# LED_004.net
KiCad netlist of a schematic drawn in EAGLE
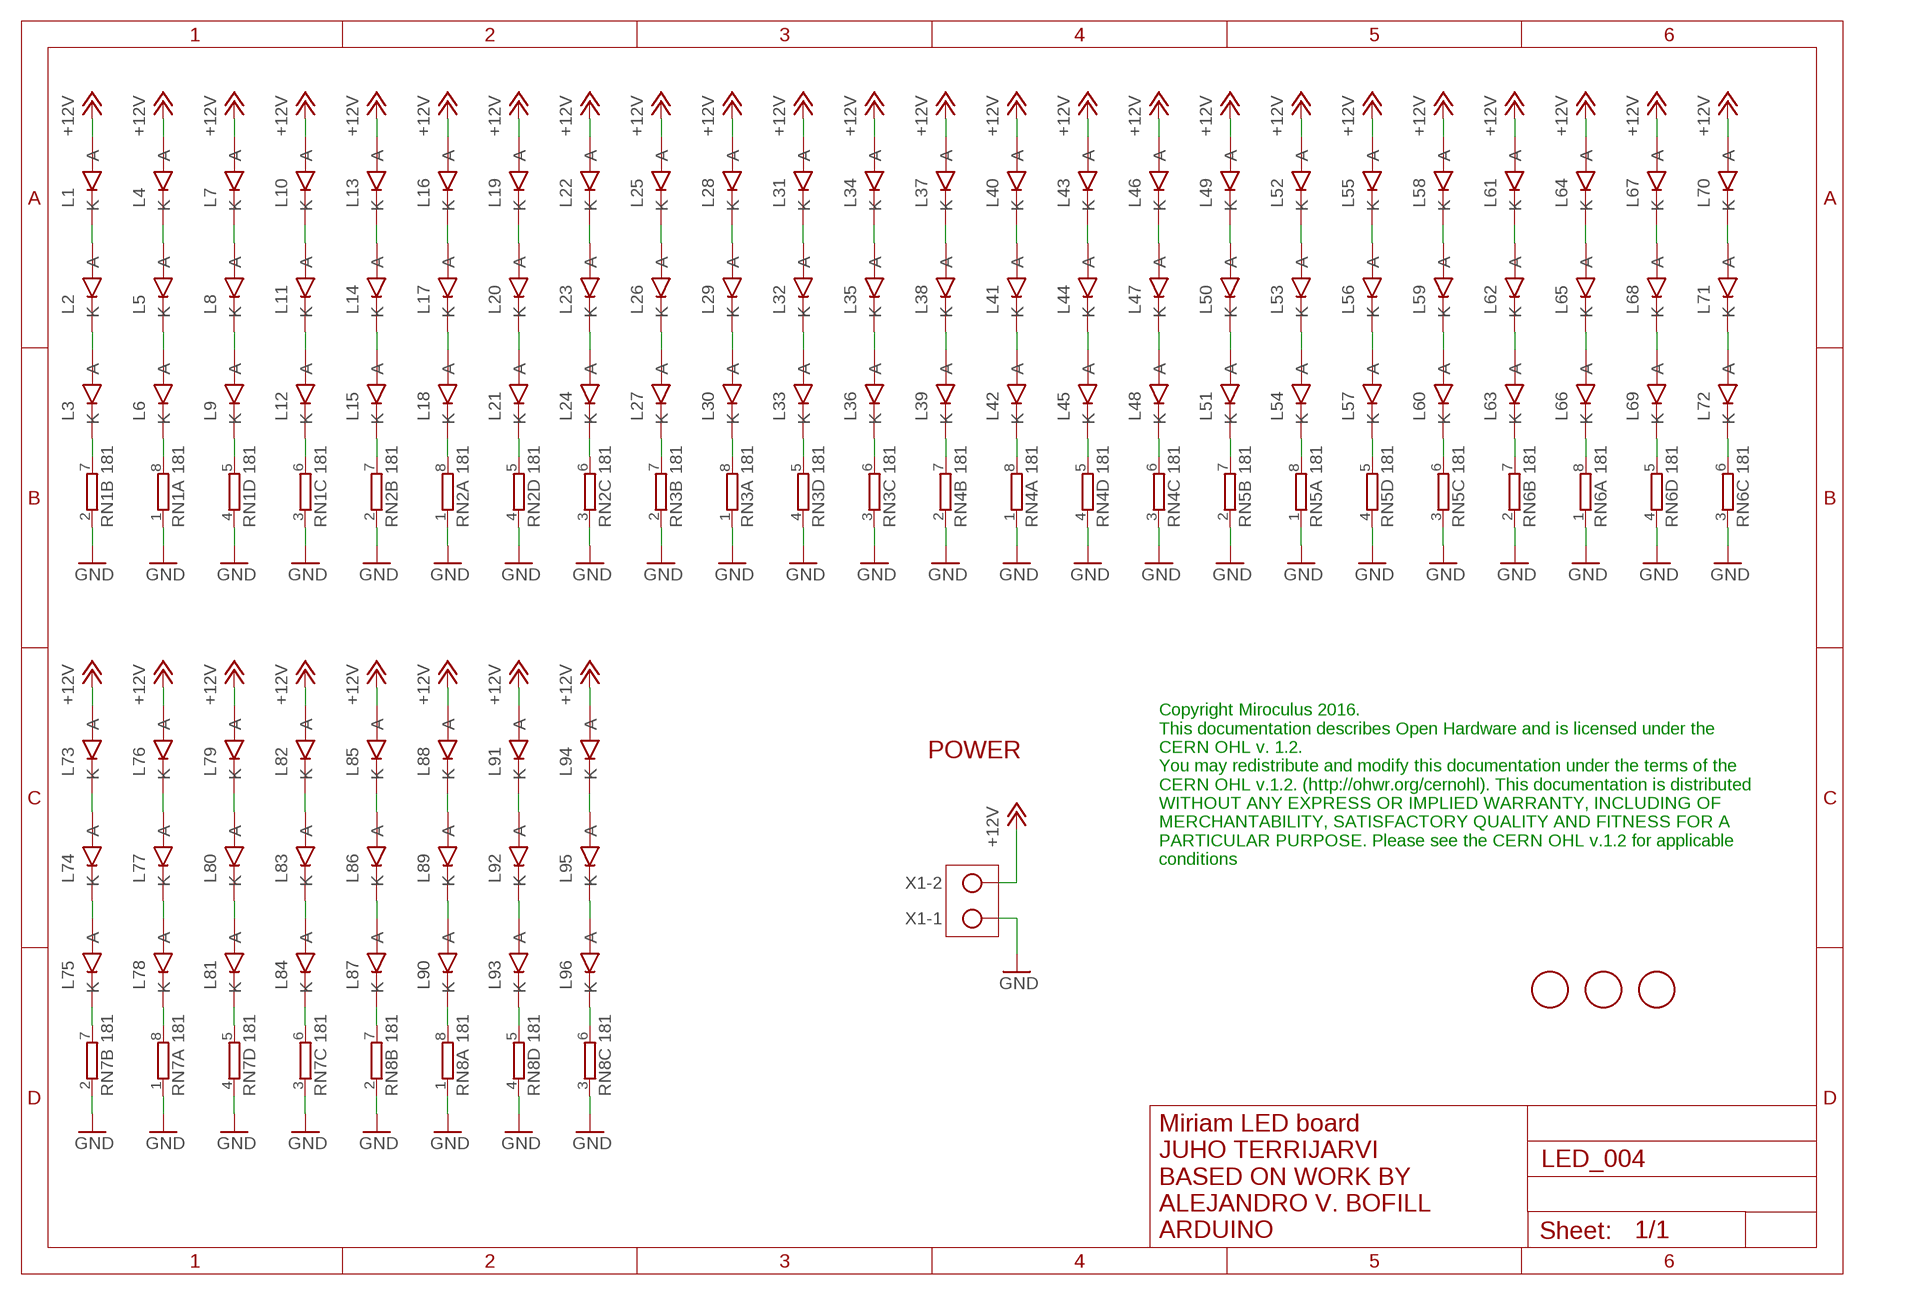
[diagram p0: schematic, sheet 1]

(export (version "E")
  (design (tool "Eeschema 10.0.6"))
  (components
    (comp (ref "FD1")
      (value "FIDUCIALMOUNT")
      (footprint "eagle-import:FIDUCIA-MOUNT")
      (libsource (lib "eagle-import") (part "FIDUCIALMOUNT"))
    )
    (comp (ref "FD2")
      (value "FIDUCIALMOUNT")
      (footprint "eagle-import:FIDUCIA-MOUNT")
      (libsource (lib "eagle-import") (part "FIDUCIALMOUNT"))
    )
    (comp (ref "FD3")
      (value "FIDUCIALMOUNT")
      (footprint "eagle-import:FIDUCIA-MOUNT")
      (libsource (lib "eagle-import") (part "FIDUCIALMOUNT"))
    )
    (comp (ref "L1")
      (value "KA-2810AQBS-G")
      (footprint "eagle-import:LED_0.2")
      (libsource (lib "eagle-import") (part "LED_0.2"))
    )
    (comp (ref "L2")
      (value "KA-2810AQBS-G")
      (footprint "eagle-import:LED_0.2")
      (libsource (lib "eagle-import") (part "LED_0.2"))
    )
    (comp (ref "L3")
      (value "KA-2810AQBS-G")
      (footprint "eagle-import:LED_0.2")
      (libsource (lib "eagle-import") (part "LED_0.2"))
    )
    (comp (ref "L4")
      (value "KA-2810AQBS-G")
      (footprint "eagle-import:LED_0.2")
      (libsource (lib "eagle-import") (part "LED_0.2"))
    )
    (comp (ref "L5")
      (value "KA-2810AQBS-G")
      (footprint "eagle-import:LED_0.2")
      (libsource (lib "eagle-import") (part "LED_0.2"))
    )
    (comp (ref "L6")
      (value "KA-2810AQBS-G")
      (footprint "eagle-import:LED_0.2")
      (libsource (lib "eagle-import") (part "LED_0.2"))
    )
    (comp (ref "L7")
      (value "KA-2810AQBS-G")
      (footprint "eagle-import:LED_0.2")
      (libsource (lib "eagle-import") (part "LED_0.2"))
    )
    (comp (ref "L8")
      (value "KA-2810AQBS-G")
      (footprint "eagle-import:LED_0.2")
      (libsource (lib "eagle-import") (part "LED_0.2"))
    )
    (comp (ref "L9")
      (value "KA-2810AQBS-G")
      (footprint "eagle-import:LED_0.2")
      (libsource (lib "eagle-import") (part "LED_0.2"))
    )
    (comp (ref "L10")
      (value "KA-2810AQBS-G")
      (footprint "eagle-import:LED_0.2")
      (libsource (lib "eagle-import") (part "LED_0.2"))
    )
    (comp (ref "L11")
      (value "KA-2810AQBS-G")
      (footprint "eagle-import:LED_0.2")
      (libsource (lib "eagle-import") (part "LED_0.2"))
    )
    (comp (ref "L12")
      (value "KA-2810AQBS-G")
      (footprint "eagle-import:LED_0.2")
      (libsource (lib "eagle-import") (part "LED_0.2"))
    )
    (comp (ref "L13")
      (value "KA-2810AQBS-G")
      (footprint "eagle-import:LED_0.2")
      (libsource (lib "eagle-import") (part "LED_0.2"))
    )
    (comp (ref "L14")
      (value "KA-2810AQBS-G")
      (footprint "eagle-import:LED_0.2")
      (libsource (lib "eagle-import") (part "LED_0.2"))
    )
    (comp (ref "L15")
      (value "KA-2810AQBS-G")
      (footprint "eagle-import:LED_0.2")
      (libsource (lib "eagle-import") (part "LED_0.2"))
    )
    (comp (ref "L16")
      (value "KA-2810AQBS-G")
      (footprint "eagle-import:LED_0.2")
      (libsource (lib "eagle-import") (part "LED_0.2"))
    )
    (comp (ref "L17")
      (value "KA-2810AQBS-G")
      (footprint "eagle-import:LED_0.2")
      (libsource (lib "eagle-import") (part "LED_0.2"))
    )
    (comp (ref "L18")
      (value "KA-2810AQBS-G")
      (footprint "eagle-import:LED_0.2")
      (libsource (lib "eagle-import") (part "LED_0.2"))
    )
    (comp (ref "L19")
      (value "KA-2810AQBS-G")
      (footprint "eagle-import:LED_0.2")
      (libsource (lib "eagle-import") (part "LED_0.2"))
    )
    (comp (ref "L20")
      (value "KA-2810AQBS-G")
      (footprint "eagle-import:LED_0.2")
      (libsource (lib "eagle-import") (part "LED_0.2"))
    )
    (comp (ref "L21")
      (value "KA-2810AQBS-G")
      (footprint "eagle-import:LED_0.2")
      (libsource (lib "eagle-import") (part "LED_0.2"))
    )
    (comp (ref "L22")
      (value "KA-2810AQBS-G")
      (footprint "eagle-import:LED_0.2")
      (libsource (lib "eagle-import") (part "LED_0.2"))
    )
    (comp (ref "L23")
      (value "KA-2810AQBS-G")
      (footprint "eagle-import:LED_0.2")
      (libsource (lib "eagle-import") (part "LED_0.2"))
    )
    (comp (ref "L24")
      (value "KA-2810AQBS-G")
      (footprint "eagle-import:LED_0.2")
      (libsource (lib "eagle-import") (part "LED_0.2"))
    )
    (comp (ref "L25")
      (value "KA-2810AQBS-G")
      (footprint "eagle-import:LED_0.2")
      (libsource (lib "eagle-import") (part "LED_0.2"))
    )
    (comp (ref "L26")
      (value "KA-2810AQBS-G")
      (footprint "eagle-import:LED_0.2")
      (libsource (lib "eagle-import") (part "LED_0.2"))
    )
    (comp (ref "L27")
      (value "KA-2810AQBS-G")
      (footprint "eagle-import:LED_0.2")
      (libsource (lib "eagle-import") (part "LED_0.2"))
    )
    (comp (ref "L28")
      (value "KA-2810AQBS-G")
      (footprint "eagle-import:LED_0.2")
      (libsource (lib "eagle-import") (part "LED_0.2"))
    )
    (comp (ref "L29")
      (value "KA-2810AQBS-G")
      (footprint "eagle-import:LED_0.2")
      (libsource (lib "eagle-import") (part "LED_0.2"))
    )
    (comp (ref "L30")
      (value "KA-2810AQBS-G")
      (footprint "eagle-import:LED_0.2")
      (libsource (lib "eagle-import") (part "LED_0.2"))
    )
    (comp (ref "L31")
      (value "KA-2810AQBS-G")
      (footprint "eagle-import:LED_0.2")
      (libsource (lib "eagle-import") (part "LED_0.2"))
    )
    (comp (ref "L32")
      (value "KA-2810AQBS-G")
      (footprint "eagle-import:LED_0.2")
      (libsource (lib "eagle-import") (part "LED_0.2"))
    )
    (comp (ref "L33")
      (value "KA-2810AQBS-G")
      (footprint "eagle-import:LED_0.2")
      (libsource (lib "eagle-import") (part "LED_0.2"))
    )
    (comp (ref "L34")
      (value "KA-2810AQBS-G")
      (footprint "eagle-import:LED_0.2")
      (libsource (lib "eagle-import") (part "LED_0.2"))
    )
    (comp (ref "L35")
      (value "KA-2810AQBS-G")
      (footprint "eagle-import:LED_0.2")
      (libsource (lib "eagle-import") (part "LED_0.2"))
    )
    (comp (ref "L36")
      (value "KA-2810AQBS-G")
      (footprint "eagle-import:LED_0.2")
      (libsource (lib "eagle-import") (part "LED_0.2"))
    )
    (comp (ref "L37")
      (value "KA-2810AQBS-G")
      (footprint "eagle-import:LED_0.2")
      (libsource (lib "eagle-import") (part "LED_0.2"))
    )
    (comp (ref "L38")
      (value "KA-2810AQBS-G")
      (footprint "eagle-import:LED_0.2")
      (libsource (lib "eagle-import") (part "LED_0.2"))
    )
    (comp (ref "L39")
      (value "KA-2810AQBS-G")
      (footprint "eagle-import:LED_0.2")
      (libsource (lib "eagle-import") (part "LED_0.2"))
    )
    (comp (ref "L40")
      (value "KA-2810AQBS-G")
      (footprint "eagle-import:LED_0.2")
      (libsource (lib "eagle-import") (part "LED_0.2"))
    )
    (comp (ref "L41")
      (value "KA-2810AQBS-G")
      (footprint "eagle-import:LED_0.2")
      (libsource (lib "eagle-import") (part "LED_0.2"))
    )
    (comp (ref "L42")
      (value "KA-2810AQBS-G")
      (footprint "eagle-import:LED_0.2")
      (libsource (lib "eagle-import") (part "LED_0.2"))
    )
    (comp (ref "L43")
      (value "KA-2810AQBS-G")
      (footprint "eagle-import:LED_0.2")
      (libsource (lib "eagle-import") (part "LED_0.2"))
    )
    (comp (ref "L44")
      (value "KA-2810AQBS-G")
      (footprint "eagle-import:LED_0.2")
      (libsource (lib "eagle-import") (part "LED_0.2"))
    )
    (comp (ref "L45")
      (value "KA-2810AQBS-G")
      (footprint "eagle-import:LED_0.2")
      (libsource (lib "eagle-import") (part "LED_0.2"))
    )
    (comp (ref "L46")
      (value "KA-2810AQBS-G")
      (footprint "eagle-import:LED_0.2")
      (libsource (lib "eagle-import") (part "LED_0.2"))
    )
    (comp (ref "L47")
      (value "KA-2810AQBS-G")
      (footprint "eagle-import:LED_0.2")
      (libsource (lib "eagle-import") (part "LED_0.2"))
    )
    (comp (ref "L48")
      (value "KA-2810AQBS-G")
      (footprint "eagle-import:LED_0.2")
      (libsource (lib "eagle-import") (part "LED_0.2"))
    )
    (comp (ref "L49")
      (value "KA-2810AQBS-G")
      (footprint "eagle-import:LED_0.2")
      (libsource (lib "eagle-import") (part "LED_0.2"))
    )
    (comp (ref "L50")
      (value "KA-2810AQBS-G")
      (footprint "eagle-import:LED_0.2")
      (libsource (lib "eagle-import") (part "LED_0.2"))
    )
    (comp (ref "L51")
      (value "KA-2810AQBS-G")
      (footprint "eagle-import:LED_0.2")
      (libsource (lib "eagle-import") (part "LED_0.2"))
    )
    (comp (ref "L52")
      (value "KA-2810AQBS-G")
      (footprint "eagle-import:LED_0.2")
      (libsource (lib "eagle-import") (part "LED_0.2"))
    )
    (comp (ref "L53")
      (value "KA-2810AQBS-G")
      (footprint "eagle-import:LED_0.2")
      (libsource (lib "eagle-import") (part "LED_0.2"))
    )
    (comp (ref "L54")
      (value "KA-2810AQBS-G")
      (footprint "eagle-import:LED_0.2")
      (libsource (lib "eagle-import") (part "LED_0.2"))
    )
    (comp (ref "L55")
      (value "KA-2810AQBS-G")
      (footprint "eagle-import:LED_0.2")
      (libsource (lib "eagle-import") (part "LED_0.2"))
    )
    (comp (ref "L56")
      (value "KA-2810AQBS-G")
      (footprint "eagle-import:LED_0.2")
      (libsource (lib "eagle-import") (part "LED_0.2"))
    )
    (comp (ref "L57")
      (value "KA-2810AQBS-G")
      (footprint "eagle-import:LED_0.2")
      (libsource (lib "eagle-import") (part "LED_0.2"))
    )
    (comp (ref "L58")
      (value "KA-2810AQBS-G")
      (footprint "eagle-import:LED_0.2")
      (libsource (lib "eagle-import") (part "LED_0.2"))
    )
    (comp (ref "L59")
      (value "KA-2810AQBS-G")
      (footprint "eagle-import:LED_0.2")
      (libsource (lib "eagle-import") (part "LED_0.2"))
    )
    (comp (ref "L60")
      (value "KA-2810AQBS-G")
      (footprint "eagle-import:LED_0.2")
      (libsource (lib "eagle-import") (part "LED_0.2"))
    )
    (comp (ref "L61")
      (value "KA-2810AQBS-G")
      (footprint "eagle-import:LED_0.2")
      (libsource (lib "eagle-import") (part "LED_0.2"))
    )
    (comp (ref "L62")
      (value "KA-2810AQBS-G")
      (footprint "eagle-import:LED_0.2")
      (libsource (lib "eagle-import") (part "LED_0.2"))
    )
    (comp (ref "L63")
      (value "KA-2810AQBS-G")
      (footprint "eagle-import:LED_0.2")
      (libsource (lib "eagle-import") (part "LED_0.2"))
    )
    (comp (ref "L64")
      (value "KA-2810AQBS-G")
      (footprint "eagle-import:LED_0.2")
      (libsource (lib "eagle-import") (part "LED_0.2"))
    )
    (comp (ref "L65")
      (value "KA-2810AQBS-G")
      (footprint "eagle-import:LED_0.2")
      (libsource (lib "eagle-import") (part "LED_0.2"))
    )
    (comp (ref "L66")
      (value "KA-2810AQBS-G")
      (footprint "eagle-import:LED_0.2")
      (libsource (lib "eagle-import") (part "LED_0.2"))
    )
    (comp (ref "L67")
      (value "KA-2810AQBS-G")
      (footprint "eagle-import:LED_0.2")
      (libsource (lib "eagle-import") (part "LED_0.2"))
    )
    (comp (ref "L68")
      (value "KA-2810AQBS-G")
      (footprint "eagle-import:LED_0.2")
      (libsource (lib "eagle-import") (part "LED_0.2"))
    )
    (comp (ref "L69")
      (value "KA-2810AQBS-G")
      (footprint "eagle-import:LED_0.2")
      (libsource (lib "eagle-import") (part "LED_0.2"))
    )
    (comp (ref "L70")
      (value "KA-2810AQBS-G")
      (footprint "eagle-import:LED_0.2")
      (libsource (lib "eagle-import") (part "LED_0.2"))
    )
    (comp (ref "L71")
      (value "KA-2810AQBS-G")
      (footprint "eagle-import:LED_0.2")
      (libsource (lib "eagle-import") (part "LED_0.2"))
    )
    (comp (ref "L72")
      (value "KA-2810AQBS-G")
      (footprint "eagle-import:LED_0.2")
      (libsource (lib "eagle-import") (part "LED_0.2"))
    )
    (comp (ref "L73")
      (value "KA-2810AQBS-G")
      (footprint "eagle-import:LED_0.2")
      (libsource (lib "eagle-import") (part "LED_0.2"))
    )
    (comp (ref "L74")
      (value "KA-2810AQBS-G")
      (footprint "eagle-import:LED_0.2")
      (libsource (lib "eagle-import") (part "LED_0.2"))
    )
    (comp (ref "L75")
      (value "KA-2810AQBS-G")
      (footprint "eagle-import:LED_0.2")
      (libsource (lib "eagle-import") (part "LED_0.2"))
    )
    (comp (ref "L76")
      (value "KA-2810AQBS-G")
      (footprint "eagle-import:LED_0.2")
      (libsource (lib "eagle-import") (part "LED_0.2"))
    )
    (comp (ref "L77")
      (value "KA-2810AQBS-G")
      (footprint "eagle-import:LED_0.2")
      (libsource (lib "eagle-import") (part "LED_0.2"))
    )
    (comp (ref "L78")
      (value "KA-2810AQBS-G")
      (footprint "eagle-import:LED_0.2")
      (libsource (lib "eagle-import") (part "LED_0.2"))
    )
    (comp (ref "L79")
      (value "KA-2810AQBS-G")
      (footprint "eagle-import:LED_0.2")
      (libsource (lib "eagle-import") (part "LED_0.2"))
    )
    (comp (ref "L80")
      (value "KA-2810AQBS-G")
      (footprint "eagle-import:LED_0.2")
      (libsource (lib "eagle-import") (part "LED_0.2"))
    )
    (comp (ref "L81")
      (value "KA-2810AQBS-G")
      (footprint "eagle-import:LED_0.2")
      (libsource (lib "eagle-import") (part "LED_0.2"))
    )
    (comp (ref "L82")
      (value "KA-2810AQBS-G")
      (footprint "eagle-import:LED_0.2")
      (libsource (lib "eagle-import") (part "LED_0.2"))
    )
    (comp (ref "L83")
      (value "KA-2810AQBS-G")
      (footprint "eagle-import:LED_0.2")
      (libsource (lib "eagle-import") (part "LED_0.2"))
    )
    (comp (ref "L84")
      (value "KA-2810AQBS-G")
      (footprint "eagle-import:LED_0.2")
      (libsource (lib "eagle-import") (part "LED_0.2"))
    )
    (comp (ref "L85")
      (value "KA-2810AQBS-G")
      (footprint "eagle-import:LED_0.2")
      (libsource (lib "eagle-import") (part "LED_0.2"))
    )
    (comp (ref "L86")
      (value "KA-2810AQBS-G")
      (footprint "eagle-import:LED_0.2")
      (libsource (lib "eagle-import") (part "LED_0.2"))
    )
    (comp (ref "L87")
      (value "KA-2810AQBS-G")
      (footprint "eagle-import:LED_0.2")
      (libsource (lib "eagle-import") (part "LED_0.2"))
    )
    (comp (ref "L88")
      (value "KA-2810AQBS-G")
      (footprint "eagle-import:LED_0.2")
      (libsource (lib "eagle-import") (part "LED_0.2"))
    )
    (comp (ref "L89")
      (value "KA-2810AQBS-G")
      (footprint "eagle-import:LED_0.2")
      (libsource (lib "eagle-import") (part "LED_0.2"))
    )
    (comp (ref "L90")
      (value "KA-2810AQBS-G")
      (footprint "eagle-import:LED_0.2")
      (libsource (lib "eagle-import") (part "LED_0.2"))
    )
    (comp (ref "L91")
      (value "KA-2810AQBS-G")
      (footprint "eagle-import:LED_0.2")
      (libsource (lib "eagle-import") (part "LED_0.2"))
    )
    (comp (ref "L92")
      (value "KA-2810AQBS-G")
      (footprint "eagle-import:LED_0.2")
      (libsource (lib "eagle-import") (part "LED_0.2"))
    )
    (comp (ref "L93")
      (value "KA-2810AQBS-G")
      (footprint "eagle-import:LED_0.2")
      (libsource (lib "eagle-import") (part "LED_0.2"))
    )
    (comp (ref "L94")
      (value "KA-2810AQBS-G")
      (footprint "eagle-import:LED_0.2")
      (libsource (lib "eagle-import") (part "LED_0.2"))
    )
    (comp (ref "L95")
      (value "KA-2810AQBS-G")
      (footprint "eagle-import:LED_0.2")
      (libsource (lib "eagle-import") (part "LED_0.2"))
    )
    (comp (ref "L96")
      (value "KA-2810AQBS-G")
      (footprint "eagle-import:LED_0.2")
      (libsource (lib "eagle-import") (part "LED_0.2"))
    )
    (comp (ref "RN1")
      (value "181")
      (footprint "eagle-import:CAY16")
      (libsource (lib "eagle-import") (part "4R-NCAY16"))
    )
    (comp (ref "RN2")
      (value "181")
      (footprint "eagle-import:CAY16")
      (libsource (lib "eagle-import") (part "4R-NCAY16"))
    )
    (comp (ref "RN3")
      (value "181")
      (footprint "eagle-import:CAY16")
      (libsource (lib "eagle-import") (part "4R-NCAY16"))
    )
    (comp (ref "RN4")
      (value "181")
      (footprint "eagle-import:CAY16")
      (libsource (lib "eagle-import") (part "4R-NCAY16"))
    )
    (comp (ref "RN5")
      (value "181")
      (footprint "eagle-import:CAY16")
      (libsource (lib "eagle-import") (part "4R-NCAY16"))
    )
    (comp (ref "RN6")
      (value "181")
      (footprint "eagle-import:CAY16")
      (libsource (lib "eagle-import") (part "4R-NCAY16"))
    )
    (comp (ref "RN7")
      (value "181")
      (footprint "eagle-import:CAY16")
      (libsource (lib "eagle-import") (part "4R-NCAY16"))
    )
    (comp (ref "RN8")
      (value "181")
      (footprint "eagle-import:CAY16")
      (libsource (lib "eagle-import") (part "4R-NCAY16"))
    )
    (comp (ref "X1")
      (value "MKDSN1,5/2-5,08")
      (footprint "eagle-import:MKDSN1,5_2-5,08")
      (libsource (lib "eagle-import") (part "MKDSN1,5/2-5,08"))
    )
  )
  (nets
    (net (code "1") (name "+12V") (class "Default")
      (node (ref "L1") (pin "2") (pinfunction "A_2") (pintype "input"))
      (node (ref "L10") (pin "2") (pinfunction "A_2") (pintype "input"))
      (node (ref "L13") (pin "2") (pinfunction "A_2") (pintype "input"))
      (node (ref "L16") (pin "2") (pinfunction "A_2") (pintype "input"))
      (node (ref "L19") (pin "2") (pinfunction "A_2") (pintype "input"))
      (node (ref "L22") (pin "2") (pinfunction "A_2") (pintype "input"))
      (node (ref "L25") (pin "2") (pinfunction "A_2") (pintype "input"))
      (node (ref "L28") (pin "2") (pinfunction "A_2") (pintype "input"))
      (node (ref "L31") (pin "2") (pinfunction "A_2") (pintype "input"))
      (node (ref "L34") (pin "2") (pinfunction "A_2") (pintype "input"))
      (node (ref "L37") (pin "2") (pinfunction "A_2") (pintype "input"))
      (node (ref "L4") (pin "2") (pinfunction "A_2") (pintype "input"))
      (node (ref "L40") (pin "2") (pinfunction "A_2") (pintype "input"))
      (node (ref "L43") (pin "2") (pinfunction "A_2") (pintype "input"))
      (node (ref "L46") (pin "2") (pinfunction "A_2") (pintype "input"))
      (node (ref "L49") (pin "2") (pinfunction "A_2") (pintype "input"))
      (node (ref "L52") (pin "2") (pinfunction "A_2") (pintype "input"))
      (node (ref "L55") (pin "2") (pinfunction "A_2") (pintype "input"))
      (node (ref "L58") (pin "2") (pinfunction "A_2") (pintype "input"))
      (node (ref "L61") (pin "2") (pinfunction "A_2") (pintype "input"))
      (node (ref "L64") (pin "2") (pinfunction "A_2") (pintype "input"))
      (node (ref "L67") (pin "2") (pinfunction "A_2") (pintype "input"))
      (node (ref "L7") (pin "2") (pinfunction "A_2") (pintype "input"))
      (node (ref "L70") (pin "2") (pinfunction "A_2") (pintype "input"))
      (node (ref "L73") (pin "2") (pinfunction "A_2") (pintype "input"))
      (node (ref "L76") (pin "2") (pinfunction "A_2") (pintype "input"))
      (node (ref "L79") (pin "2") (pinfunction "A_2") (pintype "input"))
      (node (ref "L82") (pin "2") (pinfunction "A_2") (pintype "input"))
      (node (ref "L85") (pin "2") (pinfunction "A_2") (pintype "input"))
      (node (ref "L88") (pin "2") (pinfunction "A_2") (pintype "input"))
      (node (ref "L91") (pin "2") (pinfunction "A_2") (pintype "input"))
      (node (ref "L94") (pin "2") (pinfunction "A_2") (pintype "input"))
      (node (ref "X1") (pin "2") (pinfunction "KL_2") (pintype "passive"))
    )
    (net (code "2") (name "GND") (class "Default")
      (node (ref "RN1") (pin "1") (pinfunction "1_1") (pintype "passive"))
      (node (ref "RN1") (pin "2") (pinfunction "1_2") (pintype "passive"))
      (node (ref "RN1") (pin "3") (pinfunction "1_3") (pintype "passive"))
      (node (ref "RN1") (pin "4") (pinfunction "1_4") (pintype "passive"))
      (node (ref "RN2") (pin "1") (pinfunction "1_1") (pintype "passive"))
      (node (ref "RN2") (pin "2") (pinfunction "1_2") (pintype "passive"))
      (node (ref "RN2") (pin "3") (pinfunction "1_3") (pintype "passive"))
      (node (ref "RN2") (pin "4") (pinfunction "1_4") (pintype "passive"))
      (node (ref "RN3") (pin "1") (pinfunction "1_1") (pintype "passive"))
      (node (ref "RN3") (pin "2") (pinfunction "1_2") (pintype "passive"))
      (node (ref "RN3") (pin "3") (pinfunction "1_3") (pintype "passive"))
      (node (ref "RN3") (pin "4") (pinfunction "1_4") (pintype "passive"))
      (node (ref "RN4") (pin "1") (pinfunction "1_1") (pintype "passive"))
      (node (ref "RN4") (pin "2") (pinfunction "1_2") (pintype "passive"))
      (node (ref "RN4") (pin "3") (pinfunction "1_3") (pintype "passive"))
      (node (ref "RN4") (pin "4") (pinfunction "1_4") (pintype "passive"))
      (node (ref "RN5") (pin "1") (pinfunction "1_1") (pintype "passive"))
      (node (ref "RN5") (pin "2") (pinfunction "1_2") (pintype "passive"))
      (node (ref "RN5") (pin "3") (pinfunction "1_3") (pintype "passive"))
      (node (ref "RN5") (pin "4") (pinfunction "1_4") (pintype "passive"))
      (node (ref "RN6") (pin "1") (pinfunction "1_1") (pintype "passive"))
      (node (ref "RN6") (pin "2") (pinfunction "1_2") (pintype "passive"))
      (node (ref "RN6") (pin "3") (pinfunction "1_3") (pintype "passive"))
      (node (ref "RN6") (pin "4") (pinfunction "1_4") (pintype "passive"))
      (node (ref "RN7") (pin "1") (pinfunction "1_1") (pintype "passive"))
      (node (ref "RN7") (pin "2") (pinfunction "1_2") (pintype "passive"))
      (node (ref "RN7") (pin "3") (pinfunction "1_3") (pintype "passive"))
      (node (ref "RN7") (pin "4") (pinfunction "1_4") (pintype "passive"))
      (node (ref "RN8") (pin "1") (pinfunction "1_1") (pintype "passive"))
      (node (ref "RN8") (pin "2") (pinfunction "1_2") (pintype "passive"))
      (node (ref "RN8") (pin "3") (pinfunction "1_3") (pintype "passive"))
      (node (ref "RN8") (pin "4") (pinfunction "1_4") (pintype "passive"))
      (node (ref "X1") (pin "1") (pinfunction "KL_1") (pintype "passive"))
    )
    (net (code "3") (name "Net-(L1-K)") (class "Default")
      (node (ref "L1") (pin "1") (pinfunction "K_1") (pintype "output"))
      (node (ref "L2") (pin "2") (pinfunction "A_2") (pintype "input"))
    )
    (net (code "4") (name "Net-(L2-K)") (class "Default")
      (node (ref "L2") (pin "1") (pinfunction "K_1") (pintype "output"))
      (node (ref "L3") (pin "2") (pinfunction "A_2") (pintype "input"))
    )
    (net (code "5") (name "Net-(L3-K)") (class "Default")
      (node (ref "L3") (pin "1") (pinfunction "K_1") (pintype "output"))
      (node (ref "RN1") (pin "7") (pinfunction "2_7") (pintype "passive"))
    )
    (net (code "6") (name "Net-(L4-K)") (class "Default")
      (node (ref "L4") (pin "1") (pinfunction "K_1") (pintype "output"))
      (node (ref "L5") (pin "2") (pinfunction "A_2") (pintype "input"))
    )
    (net (code "7") (name "Net-(L5-K)") (class "Default")
      (node (ref "L5") (pin "1") (pinfunction "K_1") (pintype "output"))
      (node (ref "L6") (pin "2") (pinfunction "A_2") (pintype "input"))
    )
    (net (code "8") (name "Net-(L6-K)") (class "Default")
      (node (ref "L6") (pin "1") (pinfunction "K_1") (pintype "output"))
      (node (ref "RN1") (pin "8") (pinfunction "2_8") (pintype "passive"))
    )
    (net (code "9") (name "Net-(L7-K)") (class "Default")
      (node (ref "L7") (pin "1") (pinfunction "K_1") (pintype "output"))
      (node (ref "L8") (pin "2") (pinfunction "A_2") (pintype "input"))
    )
    (net (code "10") (name "Net-(L8-K)") (class "Default")
      (node (ref "L8") (pin "1") (pinfunction "K_1") (pintype "output"))
      (node (ref "L9") (pin "2") (pinfunction "A_2") (pintype "input"))
    )
    (net (code "11") (name "Net-(L9-K)") (class "Default")
      (node (ref "L9") (pin "1") (pinfunction "K_1") (pintype "output"))
      (node (ref "RN1") (pin "5") (pinfunction "2_5") (pintype "passive"))
    )
    (net (code "12") (name "Net-(L10-K)") (class "Default")
      (node (ref "L10") (pin "1") (pinfunction "K_1") (pintype "output"))
      (node (ref "L11") (pin "2") (pinfunction "A_2") (pintype "input"))
    )
    (net (code "13") (name "Net-(L11-K)") (class "Default")
      (node (ref "L11") (pin "1") (pinfunction "K_1") (pintype "output"))
      (node (ref "L12") (pin "2") (pinfunction "A_2") (pintype "input"))
    )
    (net (code "14") (name "Net-(L12-K)") (class "Default")
      (node (ref "L12") (pin "1") (pinfunction "K_1") (pintype "output"))
      (node (ref "RN1") (pin "6") (pinfunction "2_6") (pintype "passive"))
    )
    (net (code "15") (name "Net-(L13-K)") (class "Default")
      (node (ref "L13") (pin "1") (pinfunction "K_1") (pintype "output"))
      (node (ref "L14") (pin "2") (pinfunction "A_2") (pintype "input"))
    )
    (net (code "16") (name "Net-(L14-K)") (class "Default")
      (node (ref "L14") (pin "1") (pinfunction "K_1") (pintype "output"))
      (node (ref "L15") (pin "2") (pinfunction "A_2") (pintype "input"))
    )
    (net (code "17") (name "Net-(L15-K)") (class "Default")
      (node (ref "L15") (pin "1") (pinfunction "K_1") (pintype "output"))
      (node (ref "RN2") (pin "7") (pinfunction "2_7") (pintype "passive"))
    )
    (net (code "18") (name "Net-(L16-K)") (class "Default")
      (node (ref "L16") (pin "1") (pinfunction "K_1") (pintype "output"))
      (node (ref "L17") (pin "2") (pinfunction "A_2") (pintype "input"))
    )
    (net (code "19") (name "Net-(L17-K)") (class "Default")
      (node (ref "L17") (pin "1") (pinfunction "K_1") (pintype "output"))
      (node (ref "L18") (pin "2") (pinfunction "A_2") (pintype "input"))
    )
    (net (code "20") (name "Net-(L18-K)") (class "Default")
      (node (ref "L18") (pin "1") (pinfunction "K_1") (pintype "output"))
      (node (ref "RN2") (pin "8") (pinfunction "2_8") (pintype "passive"))
    )
    (net (code "21") (name "Net-(L19-K)") (class "Default")
      (node (ref "L19") (pin "1") (pinfunction "K_1") (pintype "output"))
      (node (ref "L20") (pin "2") (pinfunction "A_2") (pintype "input"))
    )
    (net (code "22") (name "Net-(L20-K)") (class "Default")
      (node (ref "L20") (pin "1") (pinfunction "K_1") (pintype "output"))
      (node (ref "L21") (pin "2") (pinfunction "A_2") (pintype "input"))
    )
    (net (code "23") (name "Net-(L21-K)") (class "Default")
      (node (ref "L21") (pin "1") (pinfunction "K_1") (pintype "output"))
      (node (ref "RN2") (pin "5") (pinfunction "2_5") (pintype "passive"))
    )
    (net (code "24") (name "Net-(L22-K)") (class "Default")
      (node (ref "L22") (pin "1") (pinfunction "K_1") (pintype "output"))
      (node (ref "L23") (pin "2") (pinfunction "A_2") (pintype "input"))
    )
    (net (code "25") (name "Net-(L23-K)") (class "Default")
      (node (ref "L23") (pin "1") (pinfunction "K_1") (pintype "output"))
      (node (ref "L24") (pin "2") (pinfunction "A_2") (pintype "input"))
    )
    (net (code "26") (name "Net-(L24-K)") (class "Default")
      (node (ref "L24") (pin "1") (pinfunction "K_1") (pintype "output"))
      (node (ref "RN2") (pin "6") (pinfunction "2_6") (pintype "passive"))
    )
    (net (code "27") (name "Net-(L25-K)") (class "Default")
      (node (ref "L25") (pin "1") (pinfunction "K_1") (pintype "output"))
      (node (ref "L26") (pin "2") (pinfunction "A_2") (pintype "input"))
    )
    (net (code "28") (name "Net-(L26-K)") (class "Default")
      (node (ref "L26") (pin "1") (pinfunction "K_1") (pintype "output"))
      (node (ref "L27") (pin "2") (pinfunction "A_2") (pintype "input"))
    )
    (net (code "29") (name "Net-(L27-K)") (class "Default")
      (node (ref "L27") (pin "1") (pinfunction "K_1") (pintype "output"))
      (node (ref "RN3") (pin "7") (pinfunction "2_7") (pintype "passive"))
    )
    (net (code "30") (name "Net-(L28-K)") (class "Default")
      (node (ref "L28") (pin "1") (pinfunction "K_1") (pintype "output"))
      (node (ref "L29") (pin "2") (pinfunction "A_2") (pintype "input"))
    )
    (net (code "31") (name "Net-(L29-K)") (class "Default")
      (node (ref "L29") (pin "1") (pinfunction "K_1") (pintype "output"))
      (node (ref "L30") (pin "2") (pinfunction "A_2") (pintype "input"))
    )
    (net (code "32") (name "Net-(L30-K)") (class "Default")
      (node (ref "L30") (pin "1") (pinfunction "K_1") (pintype "output"))
      (node (ref "RN3") (pin "8") (pinfunction "2_8") (pintype "passive"))
    )
    (net (code "33") (name "Net-(L31-K)") (class "Default")
      (node (ref "L31") (pin "1") (pinfunction "K_1") (pintype "output"))
      (node (ref "L32") (pin "2") (pinfunction "A_2") (pintype "input"))
    )
    (net (code "34") (name "Net-(L32-K)") (class "Default")
      (node (ref "L32") (pin "1") (pinfunction "K_1") (pintype "output"))
      (node (ref "L33") (pin "2") (pinfunction "A_2") (pintype "input"))
    )
    (net (code "35") (name "Net-(L33-K)") (class "Default")
      (node (ref "L33") (pin "1") (pinfunction "K_1") (pintype "output"))
      (node (ref "RN3") (pin "5") (pinfunction "2_5") (pintype "passive"))
    )
    (net (code "36") (name "Net-(L34-K)") (class "Default")
      (node (ref "L34") (pin "1") (pinfunction "K_1") (pintype "output"))
      (node (ref "L35") (pin "2") (pinfunction "A_2") (pintype "input"))
    )
    (net (code "37") (name "Net-(L35-K)") (class "Default")
      (node (ref "L35") (pin "1") (pinfunction "K_1") (pintype "output"))
      (node (ref "L36") (pin "2") (pinfunction "A_2") (pintype "input"))
    )
    (net (code "38") (name "Net-(L36-K)") (class "Default")
      (node (ref "L36") (pin "1") (pinfunction "K_1") (pintype "output"))
      (node (ref "RN3") (pin "6") (pinfunction "2_6") (pintype "passive"))
    )
    (net (code "39") (name "Net-(L37-K)") (class "Default")
      (node (ref "L37") (pin "1") (pinfunction "K_1") (pintype "output"))
      (node (ref "L38") (pin "2") (pinfunction "A_2") (pintype "input"))
    )
    (net (code "40") (name "Net-(L38-K)") (class "Default")
      (node (ref "L38") (pin "1") (pinfunction "K_1") (pintype "output"))
      (node (ref "L39") (pin "2") (pinfunction "A_2") (pintype "input"))
    )
    (net (code "41") (name "Net-(L39-K)") (class "Default")
      (node (ref "L39") (pin "1") (pinfunction "K_1") (pintype "output"))
      (node (ref "RN4") (pin "7") (pinfunction "2_7") (pintype "passive"))
    )
    (net (code "42") (name "Net-(L40-K)") (class "Default")
      (node (ref "L40") (pin "1") (pinfunction "K_1") (pintype "output"))
      (node (ref "L41") (pin "2") (pinfunction "A_2") (pintype "input"))
    )
    (net (code "43") (name "Net-(L41-K)") (class "Default")
      (node (ref "L41") (pin "1") (pinfunction "K_1") (pintype "output"))
      (node (ref "L42") (pin "2") (pinfunction "A_2") (pintype "input"))
    )
    (net (code "44") (name "Net-(L42-K)") (class "Default")
      (node (ref "L42") (pin "1") (pinfunction "K_1") (pintype "output"))
      (node (ref "RN4") (pin "8") (pinfunction "2_8") (pintype "passive"))
    )
    (net (code "45") (name "Net-(L43-K)") (class "Default")
      (node (ref "L43") (pin "1") (pinfunction "K_1") (pintype "output"))
      (node (ref "L44") (pin "2") (pinfunction "A_2") (pintype "input"))
    )
    (net (code "46") (name "Net-(L44-K)") (class "Default")
      (node (ref "L44") (pin "1") (pinfunction "K_1") (pintype "output"))
      (node (ref "L45") (pin "2") (pinfunction "A_2") (pintype "input"))
    )
    (net (code "47") (name "Net-(L45-K)") (class "Default")
      (node (ref "L45") (pin "1") (pinfunction "K_1") (pintype "output"))
      (node (ref "RN4") (pin "5") (pinfunction "2_5") (pintype "passive"))
    )
    (net (code "48") (name "Net-(L46-K)") (class "Default")
      (node (ref "L46") (pin "1") (pinfunction "K_1") (pintype "output"))
      (node (ref "L47") (pin "2") (pinfunction "A_2") (pintype "input"))
    )
    (net (code "49") (name "Net-(L47-K)") (class "Default")
      (node (ref "L47") (pin "1") (pinfunction "K_1") (pintype "output"))
      (node (ref "L48") (pin "2") (pinfunction "A_2") (pintype "input"))
    )
    (net (code "50") (name "Net-(L48-K)") (class "Default")
      (node (ref "L48") (pin "1") (pinfunction "K_1") (pintype "output"))
      (node (ref "RN4") (pin "6") (pinfunction "2_6") (pintype "passive"))
    )
    (net (code "51") (name "Net-(L49-K)") (class "Default")
      (node (ref "L49") (pin "1") (pinfunction "K_1") (pintype "output"))
      (node (ref "L50") (pin "2") (pinfunction "A_2") (pintype "input"))
    )
    (net (code "52") (name "Net-(L50-K)") (class "Default")
      (node (ref "L50") (pin "1") (pinfunction "K_1") (pintype "output"))
      (node (ref "L51") (pin "2") (pinfunction "A_2") (pintype "input"))
    )
    (net (code "53") (name "Net-(L51-K)") (class "Default")
      (node (ref "L51") (pin "1") (pinfunction "K_1") (pintype "output"))
      (node (ref "RN5") (pin "7") (pinfunction "2_7") (pintype "passive"))
    )
    (net (code "54") (name "Net-(L52-K)") (class "Default")
      (node (ref "L52") (pin "1") (pinfunction "K_1") (pintype "output"))
      (node (ref "L53") (pin "2") (pinfunction "A_2") (pintype "input"))
    )
    (net (code "55") (name "Net-(L53-K)") (class "Default")
      (node (ref "L53") (pin "1") (pinfunction "K_1") (pintype "output"))
      (node (ref "L54") (pin "2") (pinfunction "A_2") (pintype "input"))
    )
    (net (code "56") (name "Net-(L54-K)") (class "Default")
      (node (ref "L54") (pin "1") (pinfunction "K_1") (pintype "output"))
      (node (ref "RN5") (pin "8") (pinfunction "2_8") (pintype "passive"))
    )
    (net (code "57") (name "Net-(L55-K)") (class "Default")
      (node (ref "L55") (pin "1") (pinfunction "K_1") (pintype "output"))
      (node (ref "L56") (pin "2") (pinfunction "A_2") (pintype "input"))
    )
    (net (code "58") (name "Net-(L56-K)") (class "Default")
      (node (ref "L56") (pin "1") (pinfunction "K_1") (pintype "output"))
      (node (ref "L57") (pin "2") (pinfunction "A_2") (pintype "input"))
    )
    (net (code "59") (name "Net-(L57-K)") (class "Default")
      (node (ref "L57") (pin "1") (pinfunction "K_1") (pintype "output"))
      (node (ref "RN5") (pin "5") (pinfunction "2_5") (pintype "passive"))
    )
    (net (code "60") (name "Net-(L58-K)") (class "Default")
      (node (ref "L58") (pin "1") (pinfunction "K_1") (pintype "output"))
      (node (ref "L59") (pin "2") (pinfunction "A_2") (pintype "input"))
    )
    (net (code "61") (name "Net-(L59-K)") (class "Default")
      (node (ref "L59") (pin "1") (pinfunction "K_1") (pintype "output"))
      (node (ref "L60") (pin "2") (pinfunction "A_2") (pintype "input"))
    )
    (net (code "62") (name "Net-(L60-K)") (class "Default")
      (node (ref "L60") (pin "1") (pinfunction "K_1") (pintype "output"))
      (node (ref "RN5") (pin "6") (pinfunction "2_6") (pintype "passive"))
    )
    (net (code "63") (name "Net-(L61-K)") (class "Default")
      (node (ref "L61") (pin "1") (pinfunction "K_1") (pintype "output"))
      (node (ref "L62") (pin "2") (pinfunction "A_2") (pintype "input"))
    )
    (net (code "64") (name "Net-(L62-K)") (class "Default")
      (node (ref "L62") (pin "1") (pinfunction "K_1") (pintype "output"))
      (node (ref "L63") (pin "2") (pinfunction "A_2") (pintype "input"))
    )
    (net (code "65") (name "Net-(L63-K)") (class "Default")
      (node (ref "L63") (pin "1") (pinfunction "K_1") (pintype "output"))
      (node (ref "RN6") (pin "7") (pinfunction "2_7") (pintype "passive"))
    )
    (net (code "66") (name "Net-(L64-K)") (class "Default")
      (node (ref "L64") (pin "1") (pinfunction "K_1") (pintype "output"))
      (node (ref "L65") (pin "2") (pinfunction "A_2") (pintype "input"))
    )
    (net (code "67") (name "Net-(L65-K)") (class "Default")
      (node (ref "L65") (pin "1") (pinfunction "K_1") (pintype "output"))
      (node (ref "L66") (pin "2") (pinfunction "A_2") (pintype "input"))
    )
    (net (code "68") (name "Net-(L66-K)") (class "Default")
      (node (ref "L66") (pin "1") (pinfunction "K_1") (pintype "output"))
      (node (ref "RN6") (pin "8") (pinfunction "2_8") (pintype "passive"))
    )
    (net (code "69") (name "Net-(L67-K)") (class "Default")
      (node (ref "L67") (pin "1") (pinfunction "K_1") (pintype "output"))
      (node (ref "L68") (pin "2") (pinfunction "A_2") (pintype "input"))
    )
    (net (code "70") (name "Net-(L68-K)") (class "Default")
      (node (ref "L68") (pin "1") (pinfunction "K_1") (pintype "output"))
      (node (ref "L69") (pin "2") (pinfunction "A_2") (pintype "input"))
    )
    (net (code "71") (name "Net-(L69-K)") (class "Default")
      (node (ref "L69") (pin "1") (pinfunction "K_1") (pintype "output"))
      (node (ref "RN6") (pin "5") (pinfunction "2_5") (pintype "passive"))
    )
    (net (code "72") (name "Net-(L70-K)") (class "Default")
      (node (ref "L70") (pin "1") (pinfunction "K_1") (pintype "output"))
      (node (ref "L71") (pin "2") (pinfunction "A_2") (pintype "input"))
    )
    (net (code "73") (name "Net-(L71-K)") (class "Default")
      (node (ref "L71") (pin "1") (pinfunction "K_1") (pintype "output"))
      (node (ref "L72") (pin "2") (pinfunction "A_2") (pintype "input"))
    )
    (net (code "74") (name "Net-(L72-K)") (class "Default")
      (node (ref "L72") (pin "1") (pinfunction "K_1") (pintype "output"))
      (node (ref "RN6") (pin "6") (pinfunction "2_6") (pintype "passive"))
    )
    (net (code "75") (name "Net-(L73-K)") (class "Default")
      (node (ref "L73") (pin "1") (pinfunction "K_1") (pintype "output"))
      (node (ref "L74") (pin "2") (pinfunction "A_2") (pintype "input"))
    )
    (net (code "76") (name "Net-(L74-K)") (class "Default")
      (node (ref "L74") (pin "1") (pinfunction "K_1") (pintype "output"))
      (node (ref "L75") (pin "2") (pinfunction "A_2") (pintype "input"))
    )
    (net (code "77") (name "Net-(L75-K)") (class "Default")
      (node (ref "L75") (pin "1") (pinfunction "K_1") (pintype "output"))
      (node (ref "RN7") (pin "7") (pinfunction "2_7") (pintype "passive"))
    )
    (net (code "78") (name "Net-(L76-K)") (class "Default")
      (node (ref "L76") (pin "1") (pinfunction "K_1") (pintype "output"))
      (node (ref "L77") (pin "2") (pinfunction "A_2") (pintype "input"))
    )
    (net (code "79") (name "Net-(L77-K)") (class "Default")
      (node (ref "L77") (pin "1") (pinfunction "K_1") (pintype "output"))
      (node (ref "L78") (pin "2") (pinfunction "A_2") (pintype "input"))
    )
    (net (code "80") (name "Net-(L78-K)") (class "Default")
      (node (ref "L78") (pin "1") (pinfunction "K_1") (pintype "output"))
      (node (ref "RN7") (pin "8") (pinfunction "2_8") (pintype "passive"))
    )
    (net (code "81") (name "Net-(L79-K)") (class "Default")
      (node (ref "L79") (pin "1") (pinfunction "K_1") (pintype "output"))
      (node (ref "L80") (pin "2") (pinfunction "A_2") (pintype "input"))
    )
    (net (code "82") (name "Net-(L80-K)") (class "Default")
      (node (ref "L80") (pin "1") (pinfunction "K_1") (pintype "output"))
      (node (ref "L81") (pin "2") (pinfunction "A_2") (pintype "input"))
    )
    (net (code "83") (name "Net-(L81-K)") (class "Default")
      (node (ref "L81") (pin "1") (pinfunction "K_1") (pintype "output"))
      (node (ref "RN7") (pin "5") (pinfunction "2_5") (pintype "passive"))
    )
    (net (code "84") (name "Net-(L82-K)") (class "Default")
      (node (ref "L82") (pin "1") (pinfunction "K_1") (pintype "output"))
      (node (ref "L83") (pin "2") (pinfunction "A_2") (pintype "input"))
    )
    (net (code "85") (name "Net-(L83-K)") (class "Default")
      (node (ref "L83") (pin "1") (pinfunction "K_1") (pintype "output"))
      (node (ref "L84") (pin "2") (pinfunction "A_2") (pintype "input"))
    )
    (net (code "86") (name "Net-(L84-K)") (class "Default")
      (node (ref "L84") (pin "1") (pinfunction "K_1") (pintype "output"))
      (node (ref "RN7") (pin "6") (pinfunction "2_6") (pintype "passive"))
    )
    (net (code "87") (name "Net-(L85-K)") (class "Default")
      (node (ref "L85") (pin "1") (pinfunction "K_1") (pintype "output"))
      (node (ref "L86") (pin "2") (pinfunction "A_2") (pintype "input"))
    )
    (net (code "88") (name "Net-(L86-K)") (class "Default")
      (node (ref "L86") (pin "1") (pinfunction "K_1") (pintype "output"))
      (node (ref "L87") (pin "2") (pinfunction "A_2") (pintype "input"))
    )
    (net (code "89") (name "Net-(L87-K)") (class "Default")
      (node (ref "L87") (pin "1") (pinfunction "K_1") (pintype "output"))
      (node (ref "RN8") (pin "7") (pinfunction "2_7") (pintype "passive"))
    )
    (net (code "90") (name "Net-(L88-K)") (class "Default")
      (node (ref "L88") (pin "1") (pinfunction "K_1") (pintype "output"))
      (node (ref "L89") (pin "2") (pinfunction "A_2") (pintype "input"))
    )
    (net (code "91") (name "Net-(L89-K)") (class "Default")
      (node (ref "L89") (pin "1") (pinfunction "K_1") (pintype "output"))
      (node (ref "L90") (pin "2") (pinfunction "A_2") (pintype "input"))
    )
    (net (code "92") (name "Net-(L90-K)") (class "Default")
      (node (ref "L90") (pin "1") (pinfunction "K_1") (pintype "output"))
      (node (ref "RN8") (pin "8") (pinfunction "2_8") (pintype "passive"))
    )
    (net (code "93") (name "Net-(L91-K)") (class "Default")
      (node (ref "L91") (pin "1") (pinfunction "K_1") (pintype "output"))
      (node (ref "L92") (pin "2") (pinfunction "A_2") (pintype "input"))
    )
    (net (code "94") (name "Net-(L92-K)") (class "Default")
      (node (ref "L92") (pin "1") (pinfunction "K_1") (pintype "output"))
      (node (ref "L93") (pin "2") (pinfunction "A_2") (pintype "input"))
    )
    (net (code "95") (name "Net-(L93-K)") (class "Default")
      (node (ref "L93") (pin "1") (pinfunction "K_1") (pintype "output"))
      (node (ref "RN8") (pin "5") (pinfunction "2_5") (pintype "passive"))
    )
    (net (code "96") (name "Net-(L94-K)") (class "Default")
      (node (ref "L94") (pin "1") (pinfunction "K_1") (pintype "output"))
      (node (ref "L95") (pin "2") (pinfunction "A_2") (pintype "input"))
    )
    (net (code "97") (name "Net-(L95-K)") (class "Default")
      (node (ref "L95") (pin "1") (pinfunction "K_1") (pintype "output"))
      (node (ref "L96") (pin "2") (pinfunction "A_2") (pintype "input"))
    )
    (net (code "98") (name "Net-(L96-K)") (class "Default")
      (node (ref "L96") (pin "1") (pinfunction "K_1") (pintype "output"))
      (node (ref "RN8") (pin "6") (pinfunction "2_6") (pintype "passive"))
    )
  )
)
